# zb_pt4115.net
KiCad netlist of a schematic drawn in EAGLE
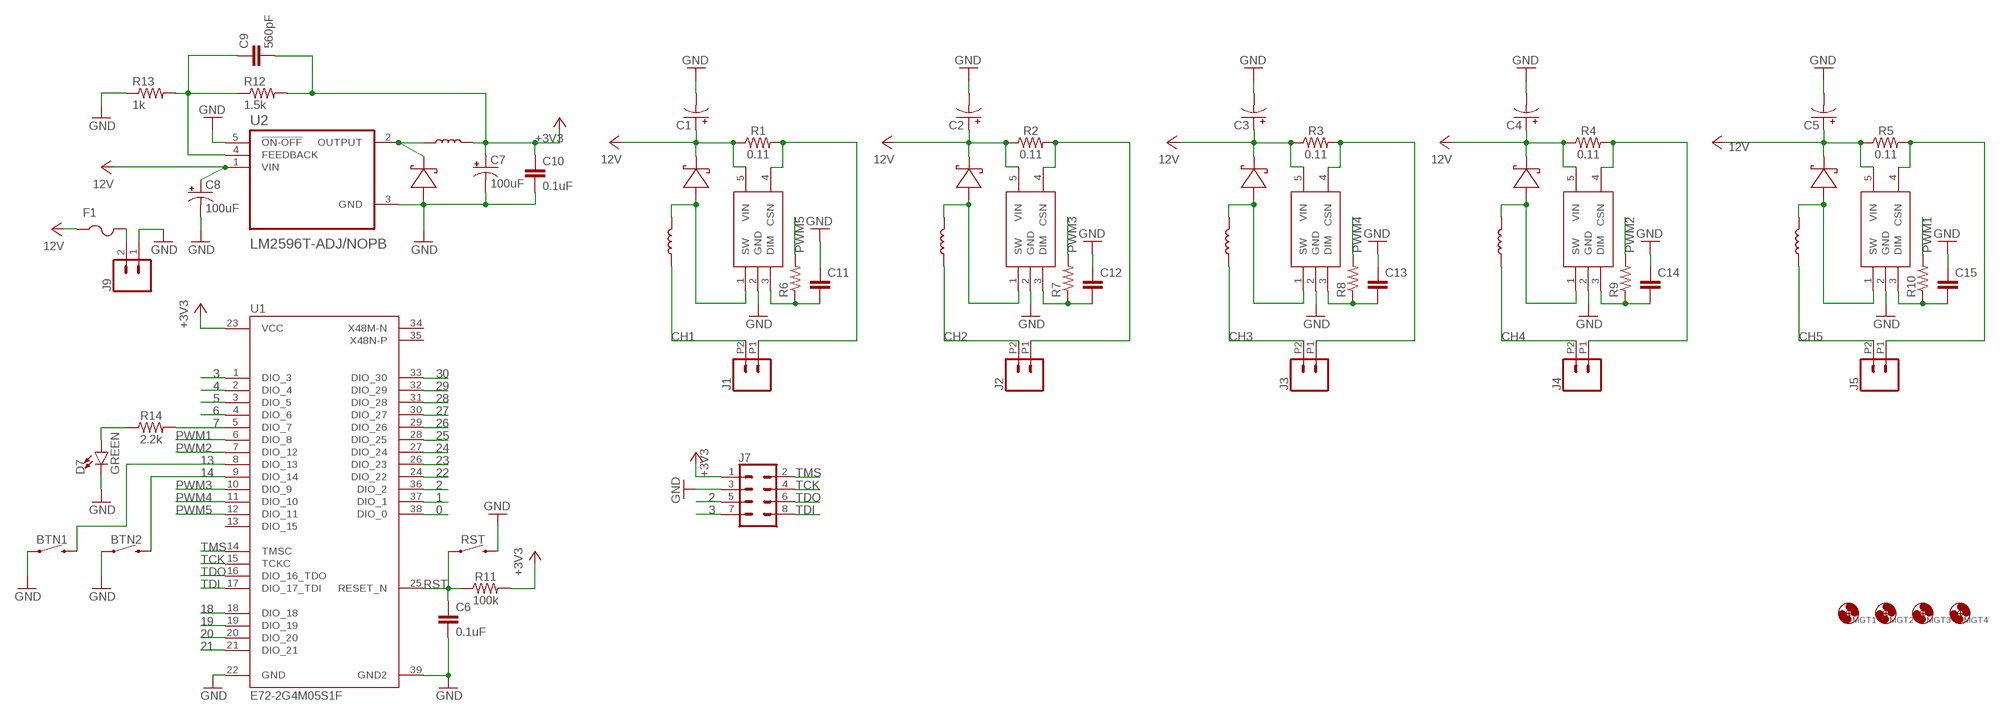
[diagram p0: schematic, sheet 1]

(export (version "E")
  (design (tool "Eeschema 10.0.6"))
  (components
    (comp (ref "BTN1")
      (value "MOMENTARY-SWITCH-SPST-SMD-5.2-REDUNDANT")
      (footprint "eagle-import:TACTILE_SWITCH_SMD_5.2MM")
      (libsource (lib "eagle-import") (part "MOMENTARY-SWITCH-SPST-SMD-5.2-REDUNDANT"))
    )
    (comp (ref "BTN2")
      (value "MOMENTARY-SWITCH-SPST-SMD-5.2-REDUNDANT")
      (footprint "eagle-import:TACTILE_SWITCH_SMD_5.2MM")
      (libsource (lib "eagle-import") (part "MOMENTARY-SWITCH-SPST-SMD-5.2-REDUNDANT"))
    )
    (comp (ref "C1")
      (value "100uF")
      (footprint "eagle-import:EIA7343")
      (libsource (lib "eagle-import") (part "100UF-POLAR-EIA7343-16V-10%(TANT)"))
    )
    (comp (ref "C2")
      (value "100uF")
      (footprint "eagle-import:EIA7343")
      (libsource (lib "eagle-import") (part "100UF-POLAR-EIA7343-16V-10%(TANT)"))
    )
    (comp (ref "C3")
      (value "100uF")
      (footprint "eagle-import:EIA7343")
      (libsource (lib "eagle-import") (part "100UF-POLAR-EIA7343-16V-10%(TANT)"))
    )
    (comp (ref "C4")
      (value "100uF")
      (footprint "eagle-import:EIA7343")
      (libsource (lib "eagle-import") (part "100UF-POLAR-EIA7343-16V-10%(TANT)"))
    )
    (comp (ref "C5")
      (value "100uF")
      (footprint "eagle-import:EIA7343")
      (libsource (lib "eagle-import") (part "100UF-POLAR-EIA7343-16V-10%(TANT)"))
    )
    (comp (ref "C6")
      (value "0.1uF")
      (footprint "eagle-import:0603")
      (libsource (lib "eagle-import") (part "0.1UF-0603-100V-10%"))
    )
    (comp (ref "C7")
      (value "100uF")
      (footprint "eagle-import:PANASONIC_D")
      (libsource (lib "eagle-import") (part "SparkFun-Capacitors_510_100UF-POLAR-25V-20%(ELEC)"))
    )
    (comp (ref "C8")
      (value "100uF")
      (footprint "eagle-import:PANASONIC_D")
      (libsource (lib "eagle-import") (part "SparkFun-Capacitors_510_100UF-POLAR-25V-20%(ELEC)"))
    )
    (comp (ref "C9")
      (value "560pF")
      (footprint "eagle-import:0603")
      (libsource (lib "eagle-import") (part "560PF-0603-50V-5%"))
    )
    (comp (ref "C10")
      (value "0.1uF")
      (footprint "eagle-import:0603")
      (libsource (lib "eagle-import") (part "0.1UF-0603-25V-5%"))
    )
    (comp (ref "C11")
      (value "100nF")
      (footprint "eagle-import:0603")
      (libsource (lib "eagle-import") (part "2.2NF/2200PF-0603-50V-10%"))
    )
    (comp (ref "C12")
      (value "100nF")
      (footprint "eagle-import:0603")
      (libsource (lib "eagle-import") (part "2.2NF/2200PF-0603-50V-10%"))
    )
    (comp (ref "C13")
      (value "100nF")
      (footprint "eagle-import:0603")
      (libsource (lib "eagle-import") (part "2.2NF/2200PF-0603-50V-10%"))
    )
    (comp (ref "C14")
      (value "100nF")
      (footprint "eagle-import:0603")
      (libsource (lib "eagle-import") (part "2.2NF/2200PF-0603-50V-10%"))
    )
    (comp (ref "C15")
      (value "100nF")
      (footprint "eagle-import:0603")
      (libsource (lib "eagle-import") (part "2.2NF/2200PF-0603-50V-10%"))
    )
    (comp (ref "D1")
      (value "SS18")
      (footprint "eagle-import:DIOM5227X270N")
      (fields (field (name "MOUSER_PART_NUMBER") "512-SS18"))
      (libsource (lib "eagle-import") (part "SS18"))
    )
    (comp (ref "D2")
      (value "SS18")
      (footprint "eagle-import:DIOM5227X270N")
      (fields (field (name "MOUSER_PART_NUMBER") "512-SS18"))
      (libsource (lib "eagle-import") (part "SS18"))
    )
    (comp (ref "D3")
      (value "SS18")
      (footprint "eagle-import:DIOM5227X270N")
      (fields (field (name "MOUSER_PART_NUMBER") "512-SS18"))
      (libsource (lib "eagle-import") (part "SS18"))
    )
    (comp (ref "D4")
      (value "SS18")
      (footprint "eagle-import:DIOM5227X270N")
      (fields (field (name "MOUSER_PART_NUMBER") "512-SS18"))
      (libsource (lib "eagle-import") (part "SS18"))
    )
    (comp (ref "D5")
      (value "SS18")
      (footprint "eagle-import:DIOM5227X270N")
      (fields (field (name "MOUSER_PART_NUMBER") "512-SS18"))
      (libsource (lib "eagle-import") (part "SS18"))
    )
    (comp (ref "D6")
      (value "SS18")
      (footprint "eagle-import:DIOM5227X270N")
      (fields (field (name "MOUSER_PART_NUMBER") "512-SS18"))
      (libsource (lib "eagle-import") (part "SS18"))
    )
    (comp (ref "D7")
      (value "GREEN")
      (footprint "eagle-import:LED-0603")
      (libsource (lib "eagle-import") (part "LED-GREEN0603"))
    )
    (comp (ref "F1")
      (value "PTCFUSE-1812")
      (footprint "eagle-import:1812")
      (libsource (lib "eagle-import") (part "PTCFUSE-1812"))
    )
    (comp (ref "IC1")
      (value "68uH")
      (footprint "eagle-import:INDPM102100X400N")
      (fields
        (field (name "MANUFACTURER_PART_NUMBER") "MSS1038-473MLB")
        (field (name "MOUSER_PART_NUMBER") "994-MSS1038-473MLB")
      )
      (libsource (lib "eagle-import") (part "MSS1038-473MLB"))
    )
    (comp (ref "IC2")
      (value "68uH")
      (footprint "eagle-import:INDPM102100X400N")
      (fields
        (field (name "MANUFACTURER_PART_NUMBER") "MSS1038-473MLB")
        (field (name "MOUSER_PART_NUMBER") "994-MSS1038-473MLB")
      )
      (libsource (lib "eagle-import") (part "MSS1038-473MLB"))
    )
    (comp (ref "IC3")
      (value "68uH")
      (footprint "eagle-import:INDPM102100X400N")
      (fields
        (field (name "MANUFACTURER_PART_NUMBER") "MSS1038-473MLB")
        (field (name "MOUSER_PART_NUMBER") "994-MSS1038-473MLB")
      )
      (libsource (lib "eagle-import") (part "MSS1038-473MLB"))
    )
    (comp (ref "IC4")
      (value "68uH")
      (footprint "eagle-import:INDPM102100X400N")
      (fields
        (field (name "MANUFACTURER_PART_NUMBER") "MSS1038-473MLB")
        (field (name "MOUSER_PART_NUMBER") "994-MSS1038-473MLB")
      )
      (libsource (lib "eagle-import") (part "MSS1038-473MLB"))
    )
    (comp (ref "IC5")
      (value "68uH")
      (footprint "eagle-import:INDPM102100X400N")
      (fields
        (field (name "MANUFACTURER_PART_NUMBER") "MSS1038-473MLB")
        (field (name "MOUSER_PART_NUMBER") "994-MSS1038-473MLB")
      )
      (libsource (lib "eagle-import") (part "MSS1038-473MLB"))
    )
    (comp (ref "IC6")
      (value "68uH")
      (footprint "eagle-import:INDPM102100X400N")
      (fields
        (field (name "MANUFACTURER_PART_NUMBER") "MSS1038-473MLB")
        (field (name "MOUSER_PART_NUMBER") "994-MSS1038-473MLB")
      )
      (libsource (lib "eagle-import") (part "MSS1038-473MLB"))
    )
    (comp (ref "J1")
      (value "CONN_022.54MM_SCREWTERM")
      (footprint "eagle-import:1X02_2.54_SCREWTERM")
      (libsource (lib "eagle-import") (part "CONN_022.54MM_SCREWTERM"))
    )
    (comp (ref "J2")
      (value "CONN_022.54MM_SCREWTERM")
      (footprint "eagle-import:1X02_2.54_SCREWTERM")
      (libsource (lib "eagle-import") (part "CONN_022.54MM_SCREWTERM"))
    )
    (comp (ref "J3")
      (value "CONN_022.54MM_SCREWTERM")
      (footprint "eagle-import:1X02_2.54_SCREWTERM")
      (libsource (lib "eagle-import") (part "CONN_022.54MM_SCREWTERM"))
    )
    (comp (ref "J4")
      (value "CONN_022.54MM_SCREWTERM")
      (footprint "eagle-import:1X02_2.54_SCREWTERM")
      (libsource (lib "eagle-import") (part "CONN_022.54MM_SCREWTERM"))
    )
    (comp (ref "J5")
      (value "CONN_022.54MM_SCREWTERM")
      (footprint "eagle-import:1X02_2.54_SCREWTERM")
      (libsource (lib "eagle-import") (part "CONN_022.54MM_SCREWTERM"))
    )
    (comp (ref "J7")
      (value "CONN_04X2")
      (footprint "eagle-import:2X4")
      (libsource (lib "eagle-import") (part "CONN_04X2"))
    )
    (comp (ref "J9")
      (value "CONN_025MM")
      (footprint "eagle-import:SCREWTERMINAL-5MM-2")
      (libsource (lib "eagle-import") (part "SparkFun-SEWPAD16_CONN_025MM"))
    )
    (comp (ref "MGT1")
      (value "MOUNT-HOLE3.0")
      (footprint "eagle-import:3,0")
      (libsource (lib "eagle-import") (part "MOUNT-HOLE3.0"))
    )
    (comp (ref "MGT2")
      (value "MOUNT-HOLE3.0")
      (footprint "eagle-import:3,0")
      (libsource (lib "eagle-import") (part "MOUNT-HOLE3.0"))
    )
    (comp (ref "MGT3")
      (value "MOUNT-HOLE3.0")
      (footprint "eagle-import:3,0")
      (libsource (lib "eagle-import") (part "MOUNT-HOLE3.0"))
    )
    (comp (ref "MGT4")
      (value "MOUNT-HOLE3.0")
      (footprint "eagle-import:3,0")
      (libsource (lib "eagle-import") (part "MOUNT-HOLE3.0"))
    )
    (comp (ref "R1")
      (value "0.11")
      (footprint "eagle-import:2010")
      (libsource (lib "eagle-import") (part "0.11OHM-2010-1/2W-1%"))
    )
    (comp (ref "R2")
      (value "0.11")
      (footprint "eagle-import:2010")
      (libsource (lib "eagle-import") (part "0.11OHM-2010-1/2W-1%"))
    )
    (comp (ref "R3")
      (value "0.11")
      (footprint "eagle-import:2010")
      (libsource (lib "eagle-import") (part "0.11OHM-2010-1/2W-1%"))
    )
    (comp (ref "R4")
      (value "0.11")
      (footprint "eagle-import:2010")
      (libsource (lib "eagle-import") (part "0.11OHM-2010-1/2W-1%"))
    )
    (comp (ref "R5")
      (value "0.11")
      (footprint "eagle-import:2010")
      (libsource (lib "eagle-import") (part "0.11OHM-2010-1/2W-1%"))
    )
    (comp (ref "R6")
      (value "100Ohm")
      (footprint "eagle-import:R0805")
      (libsource (lib "eagle-import") (part "R-US_R0805"))
    )
    (comp (ref "R7")
      (value "100Ohm")
      (footprint "eagle-import:R0805")
      (libsource (lib "eagle-import") (part "R-US_R0805"))
    )
    (comp (ref "R8")
      (value "100Ohm")
      (footprint "eagle-import:R0805")
      (libsource (lib "eagle-import") (part "R-US_R0805"))
    )
    (comp (ref "R9")
      (value "100Ohm")
      (footprint "eagle-import:R0805")
      (libsource (lib "eagle-import") (part "R-US_R0805"))
    )
    (comp (ref "R10")
      (value "100Ohm")
      (footprint "eagle-import:R0805")
      (libsource (lib "eagle-import") (part "R-US_R0805"))
    )
    (comp (ref "R11")
      (value "100k")
      (footprint "eagle-import:0603")
      (libsource (lib "eagle-import") (part "100KOHM-0603-1/10W-1%"))
    )
    (comp (ref "R12")
      (value "1.5k")
      (footprint "eagle-import:R0805")
      (libsource (lib "eagle-import") (part "R-US_R0805"))
    )
    (comp (ref "R13")
      (value "1k")
      (footprint "eagle-import:R0805")
      (libsource (lib "eagle-import") (part "R-US_R0805"))
    )
    (comp (ref "R14")
      (value "2.2k")
      (footprint "eagle-import:0603")
      (libsource (lib "eagle-import") (part "2.2KOHM-0603-1/10W-1%"))
    )
    (comp (ref "RST")
      (value "MOMENTARY-SWITCH-SPST-SMD-5.2-REDUNDANT")
      (footprint "eagle-import:TACTILE_SWITCH_SMD_5.2MM")
      (libsource (lib "eagle-import") (part "MOMENTARY-SWITCH-SPST-SMD-5.2-REDUNDANT"))
    )
    (comp (ref "U$1")
      (value "PT4115")
      (footprint "eagle-import:SOT-89-5")
      (fields (field (name "MF") "Pulse"))
      (libsource (lib "eagle-import") (part "PT4115"))
    )
    (comp (ref "U$2")
      (value "PT4115")
      (footprint "eagle-import:SOT-89-5")
      (fields (field (name "MF") "Pulse"))
      (libsource (lib "eagle-import") (part "PT4115"))
    )
    (comp (ref "U$3")
      (value "PT4115")
      (footprint "eagle-import:SOT-89-5")
      (fields (field (name "MF") "Pulse"))
      (libsource (lib "eagle-import") (part "PT4115"))
    )
    (comp (ref "U$4")
      (value "PT4115")
      (footprint "eagle-import:SOT-89-5")
      (fields (field (name "MF") "Pulse"))
      (libsource (lib "eagle-import") (part "PT4115"))
    )
    (comp (ref "U$5")
      (value "PT4115")
      (footprint "eagle-import:SOT-89-5")
      (fields (field (name "MF") "Pulse"))
      (libsource (lib "eagle-import") (part "PT4115"))
    )
    (comp (ref "U1")
      (value "E72-2G4M05S1F")
      (footprint "eagle-import:E72-2G4M05S1F")
      (libsource (lib "eagle-import") (part "E72-2G4M05S1F"))
    )
    (comp (ref "U2")
      (value "LM2596T-ADJ/NOPB")
      (footprint "eagle-import:TO170P1016X470X2092-5")
      (fields (field (name "MF") "Texas Instruments"))
      (libsource (lib "eagle-import") (part "LM2596T-ADJ/NOPB"))
    )
  )
  (nets
    (net (code "1") (name "+3V3") (class "Default")
      (node (ref "C10") (pin "1") (pinfunction "1_1") (pintype "passive"))
      (node (ref "C7") (pin "+") (pinfunction "+_+") (pintype "passive"))
      (node (ref "C9") (pin "2") (pinfunction "2_2") (pintype "passive"))
      (node (ref "IC6") (pin "2") (pinfunction "2_2") (pintype "bidirectional"))
      (node (ref "J7") (pin "1") (pinfunction "1_1") (pintype "passive"))
      (node (ref "R11") (pin "2") (pinfunction "2_2") (pintype "passive"))
      (node (ref "R12") (pin "2") (pinfunction "2_2") (pintype "passive"))
      (node (ref "U1") (pin "23") (pinfunction "VCC_23") (pintype "bidirectional"))
    )
    (net (code "2") (name "/0") (class "Default")
      (node (ref "U1") (pin "38") (pinfunction "DIO_0_38") (pintype "bidirectional"))
    )
    (net (code "3") (name "/1") (class "Default")
      (node (ref "U1") (pin "37") (pinfunction "DIO_1_37") (pintype "bidirectional"))
    )
    (net (code "4") (name "/2") (class "Default")
      (node (ref "J7") (pin "5") (pinfunction "5_5") (pintype "passive"))
      (node (ref "U1") (pin "36") (pinfunction "DIO_2_36") (pintype "bidirectional"))
    )
    (net (code "5") (name "/3") (class "Default")
      (node (ref "J7") (pin "7") (pinfunction "7_7") (pintype "passive"))
      (node (ref "U1") (pin "1") (pinfunction "DIO_3_1") (pintype "bidirectional"))
    )
    (net (code "6") (name "/4") (class "Default")
      (node (ref "U1") (pin "2") (pinfunction "DIO_4_2") (pintype "bidirectional"))
    )
    (net (code "7") (name "/5") (class "Default")
      (node (ref "U1") (pin "3") (pinfunction "DIO_5_3") (pintype "bidirectional"))
    )
    (net (code "8") (name "/6") (class "Default")
      (node (ref "U1") (pin "4") (pinfunction "DIO_6_4") (pintype "bidirectional"))
    )
    (net (code "9") (name "/7") (class "Default")
      (node (ref "R14") (pin "2") (pinfunction "2_2") (pintype "passive"))
      (node (ref "U1") (pin "5") (pinfunction "DIO_7_5") (pintype "bidirectional"))
    )
    (net (code "10") (name "/13") (class "Default")
      (node (ref "BTN1") (pin "3") (pinfunction "2_3") (pintype "passive"))
      (node (ref "BTN1") (pin "4") (pinfunction "2_4") (pintype "passive"))
      (node (ref "U1") (pin "8") (pinfunction "DIO_13_8") (pintype "bidirectional"))
    )
    (net (code "11") (name "/14") (class "Default")
      (node (ref "BTN2") (pin "3") (pinfunction "2_3") (pintype "passive"))
      (node (ref "BTN2") (pin "4") (pinfunction "2_4") (pintype "passive"))
      (node (ref "U1") (pin "9") (pinfunction "DIO_14_9") (pintype "bidirectional"))
    )
    (net (code "12") (name "/18") (class "Default")
      (node (ref "U1") (pin "18") (pinfunction "DIO_18_18") (pintype "bidirectional"))
    )
    (net (code "13") (name "/19") (class "Default")
      (node (ref "U1") (pin "19") (pinfunction "DIO_19_19") (pintype "bidirectional"))
    )
    (net (code "14") (name "/20") (class "Default")
      (node (ref "U1") (pin "20") (pinfunction "DIO_20_20") (pintype "bidirectional"))
    )
    (net (code "15") (name "/21") (class "Default")
      (node (ref "U1") (pin "21") (pinfunction "DIO_21_21") (pintype "bidirectional"))
    )
    (net (code "16") (name "/22") (class "Default")
      (node (ref "U1") (pin "24") (pinfunction "DIO_22_24") (pintype "bidirectional"))
    )
    (net (code "17") (name "/23") (class "Default")
      (node (ref "U1") (pin "26") (pinfunction "DIO_23_26") (pintype "bidirectional"))
    )
    (net (code "18") (name "/24") (class "Default")
      (node (ref "U1") (pin "27") (pinfunction "DIO_24_27") (pintype "bidirectional"))
    )
    (net (code "19") (name "/25") (class "Default")
      (node (ref "U1") (pin "28") (pinfunction "DIO_25_28") (pintype "bidirectional"))
    )
    (net (code "20") (name "/26") (class "Default")
      (node (ref "U1") (pin "29") (pinfunction "DIO_26_29") (pintype "bidirectional"))
    )
    (net (code "21") (name "/27") (class "Default")
      (node (ref "U1") (pin "30") (pinfunction "DIO_27_30") (pintype "bidirectional"))
    )
    (net (code "22") (name "/28") (class "Default")
      (node (ref "U1") (pin "31") (pinfunction "DIO_28_31") (pintype "bidirectional"))
    )
    (net (code "23") (name "/29") (class "Default")
      (node (ref "U1") (pin "32") (pinfunction "DIO_29_32") (pintype "bidirectional"))
    )
    (net (code "24") (name "/30") (class "Default")
      (node (ref "U1") (pin "33") (pinfunction "DIO_30_33") (pintype "bidirectional"))
    )
    (net (code "25") (name "/CH1") (class "Default")
      (node (ref "IC1") (pin "1") (pinfunction "1_1") (pintype "bidirectional"))
      (node (ref "J1") (pin "P2") (pinfunction "2_P2") (pintype "passive"))
    )
    (net (code "26") (name "/CH2") (class "Default")
      (node (ref "IC2") (pin "1") (pinfunction "1_1") (pintype "bidirectional"))
      (node (ref "J2") (pin "P2") (pinfunction "2_P2") (pintype "passive"))
    )
    (net (code "27") (name "/CH3") (class "Default")
      (node (ref "IC3") (pin "1") (pinfunction "1_1") (pintype "bidirectional"))
      (node (ref "J3") (pin "P2") (pinfunction "2_P2") (pintype "passive"))
    )
    (net (code "28") (name "/CH4") (class "Default")
      (node (ref "IC4") (pin "1") (pinfunction "1_1") (pintype "bidirectional"))
      (node (ref "J4") (pin "P2") (pinfunction "2_P2") (pintype "passive"))
    )
    (net (code "29") (name "/CH5") (class "Default")
      (node (ref "IC5") (pin "1") (pinfunction "1_1") (pintype "bidirectional"))
      (node (ref "J5") (pin "P2") (pinfunction "2_P2") (pintype "passive"))
    )
    (net (code "30") (name "/PWM1") (class "Default")
      (node (ref "R10") (pin "2") (pinfunction "2_2") (pintype "passive"))
      (node (ref "U1") (pin "6") (pinfunction "DIO_8_6") (pintype "bidirectional"))
    )
    (net (code "31") (name "/PWM2") (class "Default")
      (node (ref "R9") (pin "2") (pinfunction "2_2") (pintype "passive"))
      (node (ref "U1") (pin "7") (pinfunction "DIO_12_7") (pintype "bidirectional"))
    )
    (net (code "32") (name "/PWM3") (class "Default")
      (node (ref "R7") (pin "2") (pinfunction "2_2") (pintype "passive"))
      (node (ref "U1") (pin "10") (pinfunction "DIO_9_10") (pintype "bidirectional"))
    )
    (net (code "33") (name "/PWM4") (class "Default")
      (node (ref "R8") (pin "2") (pinfunction "2_2") (pintype "passive"))
      (node (ref "U1") (pin "11") (pinfunction "DIO_10_11") (pintype "bidirectional"))
    )
    (net (code "34") (name "/PWM5") (class "Default")
      (node (ref "R6") (pin "2") (pinfunction "2_2") (pintype "passive"))
      (node (ref "U1") (pin "12") (pinfunction "DIO_11_12") (pintype "bidirectional"))
    )
    (net (code "35") (name "/RST") (class "Default")
      (node (ref "C6") (pin "1") (pinfunction "1_1") (pintype "passive"))
      (node (ref "R11") (pin "1") (pinfunction "1_1") (pintype "passive"))
      (node (ref "RST") (pin "1") (pinfunction "1_1") (pintype "passive"))
      (node (ref "RST") (pin "2") (pinfunction "1_2") (pintype "passive"))
      (node (ref "U1") (pin "25") (pinfunction "RESET_N_25") (pintype "bidirectional"))
    )
    (net (code "36") (name "/TCK") (class "Default")
      (node (ref "J7") (pin "4") (pinfunction "4_4") (pintype "passive"))
      (node (ref "U1") (pin "15") (pinfunction "TCKC_15") (pintype "bidirectional"))
    )
    (net (code "37") (name "/TDI") (class "Default")
      (node (ref "J7") (pin "8") (pinfunction "8_8") (pintype "passive"))
      (node (ref "U1") (pin "17") (pinfunction "DIO_17_TDI_17") (pintype "bidirectional"))
    )
    (net (code "38") (name "/TDO") (class "Default")
      (node (ref "J7") (pin "6") (pinfunction "6_6") (pintype "passive"))
      (node (ref "U1") (pin "16") (pinfunction "DIO_16_TDO_16") (pintype "bidirectional"))
    )
    (net (code "39") (name "/TMS") (class "Default")
      (node (ref "J7") (pin "2") (pinfunction "2_2") (pintype "passive"))
      (node (ref "U1") (pin "14") (pinfunction "TMSC_14") (pintype "bidirectional"))
    )
    (net (code "40") (name "12V") (class "Default")
      (node (ref "C1") (pin "A") (pinfunction "+_A") (pintype "passive"))
      (node (ref "C2") (pin "A") (pinfunction "+_A") (pintype "passive"))
      (node (ref "C3") (pin "A") (pinfunction "+_A") (pintype "passive"))
      (node (ref "C4") (pin "A") (pinfunction "+_A") (pintype "passive"))
      (node (ref "C5") (pin "A") (pinfunction "+_A") (pintype "passive"))
      (node (ref "C8") (pin "+") (pinfunction "+_+") (pintype "passive"))
      (node (ref "D1") (pin "1") (pinfunction "K_1") (pintype "bidirectional"))
      (node (ref "D2") (pin "1") (pinfunction "K_1") (pintype "bidirectional"))
      (node (ref "D3") (pin "1") (pinfunction "K_1") (pintype "bidirectional"))
      (node (ref "D4") (pin "1") (pinfunction "K_1") (pintype "bidirectional"))
      (node (ref "D5") (pin "1") (pinfunction "K_1") (pintype "bidirectional"))
      (node (ref "F1") (pin "1") (pinfunction "1_1") (pintype "passive"))
      (node (ref "F1") (pin "2") (pinfunction "2_2") (pintype "passive"))
      (node (ref "J9") (pin "2") (pinfunction "2_2") (pintype "passive"))
      (node (ref "R1") (pin "1") (pinfunction "1_1") (pintype "passive"))
      (node (ref "R2") (pin "1") (pinfunction "1_1") (pintype "passive"))
      (node (ref "R3") (pin "1") (pinfunction "1_1") (pintype "passive"))
      (node (ref "R4") (pin "1") (pinfunction "1_1") (pintype "passive"))
      (node (ref "R5") (pin "1") (pinfunction "1_1") (pintype "passive"))
      (node (ref "U$1") (pin "5") (pinfunction "VIN_5") (pintype "bidirectional"))
      (node (ref "U$2") (pin "5") (pinfunction "VIN_5") (pintype "bidirectional"))
      (node (ref "U$3") (pin "5") (pinfunction "VIN_5") (pintype "bidirectional"))
      (node (ref "U$4") (pin "5") (pinfunction "VIN_5") (pintype "bidirectional"))
      (node (ref "U$5") (pin "5") (pinfunction "VIN_5") (pintype "bidirectional"))
      (node (ref "U2") (pin "1") (pinfunction "VIN_1") (pintype "input"))
    )
    (net (code "41") (name "GND") (class "Default")
      (node (ref "BTN1") (pin "1") (pinfunction "1_1") (pintype "passive"))
      (node (ref "BTN1") (pin "2") (pinfunction "1_2") (pintype "passive"))
      (node (ref "BTN2") (pin "1") (pinfunction "1_1") (pintype "passive"))
      (node (ref "BTN2") (pin "2") (pinfunction "1_2") (pintype "passive"))
      (node (ref "C1") (pin "C") (pinfunction "-_C") (pintype "passive"))
      (node (ref "C10") (pin "2") (pinfunction "2_2") (pintype "passive"))
      (node (ref "C11") (pin "1") (pinfunction "1_1") (pintype "passive"))
      (node (ref "C12") (pin "1") (pinfunction "1_1") (pintype "passive"))
      (node (ref "C13") (pin "1") (pinfunction "1_1") (pintype "passive"))
      (node (ref "C14") (pin "1") (pinfunction "1_1") (pintype "passive"))
      (node (ref "C15") (pin "1") (pinfunction "1_1") (pintype "passive"))
      (node (ref "C2") (pin "C") (pinfunction "-_C") (pintype "passive"))
      (node (ref "C3") (pin "C") (pinfunction "-_C") (pintype "passive"))
      (node (ref "C4") (pin "C") (pinfunction "-_C") (pintype "passive"))
      (node (ref "C5") (pin "C") (pinfunction "-_C") (pintype "passive"))
      (node (ref "C6") (pin "2") (pinfunction "2_2") (pintype "passive"))
      (node (ref "C7") (pin "-") (pinfunction "-_-") (pintype "passive"))
      (node (ref "C8") (pin "-") (pinfunction "-_-") (pintype "passive"))
      (node (ref "D6") (pin "2") (pinfunction "A_2") (pintype "bidirectional"))
      (node (ref "D7") (pin "C") (pinfunction "C_C") (pintype "passive"))
      (node (ref "J7") (pin "3") (pinfunction "3_3") (pintype "passive"))
      (node (ref "J9") (pin "1") (pinfunction "1_1") (pintype "passive"))
      (node (ref "R13") (pin "1") (pinfunction "1_1") (pintype "passive"))
      (node (ref "RST") (pin "3") (pinfunction "2_3") (pintype "passive"))
      (node (ref "RST") (pin "4") (pinfunction "2_4") (pintype "passive"))
      (node (ref "U$1") (pin "2") (pinfunction "GND_2") (pintype "bidirectional"))
      (node (ref "U$2") (pin "2") (pinfunction "GND_2") (pintype "bidirectional"))
      (node (ref "U$3") (pin "2") (pinfunction "GND_2") (pintype "bidirectional"))
      (node (ref "U$4") (pin "2") (pinfunction "GND_2") (pintype "bidirectional"))
      (node (ref "U$5") (pin "2") (pinfunction "GND_2") (pintype "bidirectional"))
      (node (ref "U1") (pin "22") (pinfunction "GND_22") (pintype "bidirectional"))
      (node (ref "U1") (pin "39") (pinfunction "GND2_39") (pintype "bidirectional"))
      (node (ref "U2") (pin "3") (pinfunction "GND_3") (pintype "power_in"))
      (node (ref "U2") (pin "5") (pinfunction "~{ON-OFF}_5") (pintype "input"))
    )
    (net (code "42") (name "Net-(D1-A)") (class "Default")
      (node (ref "D1") (pin "2") (pinfunction "A_2") (pintype "bidirectional"))
      (node (ref "IC1") (pin "2") (pinfunction "2_2") (pintype "bidirectional"))
      (node (ref "U$1") (pin "1") (pinfunction "SW_1") (pintype "bidirectional"))
    )
    (net (code "43") (name "Net-(D2-A)") (class "Default")
      (node (ref "D2") (pin "2") (pinfunction "A_2") (pintype "bidirectional"))
      (node (ref "IC2") (pin "2") (pinfunction "2_2") (pintype "bidirectional"))
      (node (ref "U$2") (pin "1") (pinfunction "SW_1") (pintype "bidirectional"))
    )
    (net (code "44") (name "Net-(D3-A)") (class "Default")
      (node (ref "D3") (pin "2") (pinfunction "A_2") (pintype "bidirectional"))
      (node (ref "IC3") (pin "2") (pinfunction "2_2") (pintype "bidirectional"))
      (node (ref "U$3") (pin "1") (pinfunction "SW_1") (pintype "bidirectional"))
    )
    (net (code "45") (name "Net-(D4-A)") (class "Default")
      (node (ref "D4") (pin "2") (pinfunction "A_2") (pintype "bidirectional"))
      (node (ref "IC4") (pin "2") (pinfunction "2_2") (pintype "bidirectional"))
      (node (ref "U$4") (pin "1") (pinfunction "SW_1") (pintype "bidirectional"))
    )
    (net (code "46") (name "Net-(D5-A)") (class "Default")
      (node (ref "D5") (pin "2") (pinfunction "A_2") (pintype "bidirectional"))
      (node (ref "IC5") (pin "2") (pinfunction "2_2") (pintype "bidirectional"))
      (node (ref "U$5") (pin "1") (pinfunction "SW_1") (pintype "bidirectional"))
    )
    (net (code "47") (name "Net-(D6-K)") (class "Default")
      (node (ref "D6") (pin "1") (pinfunction "K_1") (pintype "bidirectional"))
      (node (ref "IC6") (pin "1") (pinfunction "1_1") (pintype "bidirectional"))
      (node (ref "U2") (pin "2") (pinfunction "OUTPUT_2") (pintype "output"))
    )
    (net (code "48") (name "Net-(D7-PadA)") (class "Default")
      (node (ref "D7") (pin "A") (pinfunction "A_A") (pintype "passive"))
      (node (ref "R14") (pin "1") (pinfunction "1_1") (pintype "passive"))
    )
    (net (code "49") (name "Net-(J1-1)") (class "Default")
      (node (ref "J1") (pin "P1") (pinfunction "1_P1") (pintype "passive"))
      (node (ref "R1") (pin "2") (pinfunction "2_2") (pintype "passive"))
      (node (ref "U$1") (pin "4") (pinfunction "CSN_4") (pintype "bidirectional"))
    )
    (net (code "50") (name "Net-(J2-1)") (class "Default")
      (node (ref "J2") (pin "P1") (pinfunction "1_P1") (pintype "passive"))
      (node (ref "R2") (pin "2") (pinfunction "2_2") (pintype "passive"))
      (node (ref "U$2") (pin "4") (pinfunction "CSN_4") (pintype "bidirectional"))
    )
    (net (code "51") (name "Net-(J3-1)") (class "Default")
      (node (ref "J3") (pin "P1") (pinfunction "1_P1") (pintype "passive"))
      (node (ref "R3") (pin "2") (pinfunction "2_2") (pintype "passive"))
      (node (ref "U$3") (pin "4") (pinfunction "CSN_4") (pintype "bidirectional"))
    )
    (net (code "52") (name "Net-(J4-1)") (class "Default")
      (node (ref "J4") (pin "P1") (pinfunction "1_P1") (pintype "passive"))
      (node (ref "R4") (pin "2") (pinfunction "2_2") (pintype "passive"))
      (node (ref "U$4") (pin "4") (pinfunction "CSN_4") (pintype "bidirectional"))
    )
    (net (code "53") (name "Net-(J5-1)") (class "Default")
      (node (ref "J5") (pin "P1") (pinfunction "1_P1") (pintype "passive"))
      (node (ref "R5") (pin "2") (pinfunction "2_2") (pintype "passive"))
      (node (ref "U$5") (pin "4") (pinfunction "CSN_4") (pintype "bidirectional"))
    )
    (net (code "54") (name "Net-(U$1-DIM)") (class "Default")
      (node (ref "C11") (pin "2") (pinfunction "2_2") (pintype "passive"))
      (node (ref "R6") (pin "1") (pinfunction "1_1") (pintype "passive"))
      (node (ref "U$1") (pin "3") (pinfunction "DIM_3") (pintype "bidirectional"))
    )
    (net (code "55") (name "Net-(U$2-DIM)") (class "Default")
      (node (ref "C12") (pin "2") (pinfunction "2_2") (pintype "passive"))
      (node (ref "R7") (pin "1") (pinfunction "1_1") (pintype "passive"))
      (node (ref "U$2") (pin "3") (pinfunction "DIM_3") (pintype "bidirectional"))
    )
    (net (code "56") (name "Net-(U$3-DIM)") (class "Default")
      (node (ref "C13") (pin "2") (pinfunction "2_2") (pintype "passive"))
      (node (ref "R8") (pin "1") (pinfunction "1_1") (pintype "passive"))
      (node (ref "U$3") (pin "3") (pinfunction "DIM_3") (pintype "bidirectional"))
    )
    (net (code "57") (name "Net-(U$4-DIM)") (class "Default")
      (node (ref "C14") (pin "2") (pinfunction "2_2") (pintype "passive"))
      (node (ref "R9") (pin "1") (pinfunction "1_1") (pintype "passive"))
      (node (ref "U$4") (pin "3") (pinfunction "DIM_3") (pintype "bidirectional"))
    )
    (net (code "58") (name "Net-(U$5-DIM)") (class "Default")
      (node (ref "C15") (pin "2") (pinfunction "2_2") (pintype "passive"))
      (node (ref "R10") (pin "1") (pinfunction "1_1") (pintype "passive"))
      (node (ref "U$5") (pin "3") (pinfunction "DIM_3") (pintype "bidirectional"))
    )
    (net (code "59") (name "Net-(U2-FEEDBACK)") (class "Default")
      (node (ref "C9") (pin "1") (pinfunction "1_1") (pintype "passive"))
      (node (ref "R12") (pin "1") (pinfunction "1_1") (pintype "passive"))
      (node (ref "R13") (pin "2") (pinfunction "2_2") (pintype "passive"))
      (node (ref "U2") (pin "4") (pinfunction "FEEDBACK_4") (pintype "input"))
    )
    (net (code "60") (name "unconnected-(U1-DIO_15-Pad13)") (class "Default")
      (node (ref "U1") (pin "13") (pinfunction "DIO_15_13") (pintype "bidirectional"))
    )
    (net (code "61") (name "unconnected-(U1-X48M-N-Pad34)") (class "Default")
      (node (ref "U1") (pin "34") (pinfunction "X48M-N_34") (pintype "bidirectional"))
    )
    (net (code "62") (name "unconnected-(U1-X48N-P-Pad35)") (class "Default")
      (node (ref "U1") (pin "35") (pinfunction "X48N-P_35") (pintype "bidirectional"))
    )
  )
)
